# StandBy_converter.net
KiCad netlist of a schematic drawn in Altium Designer
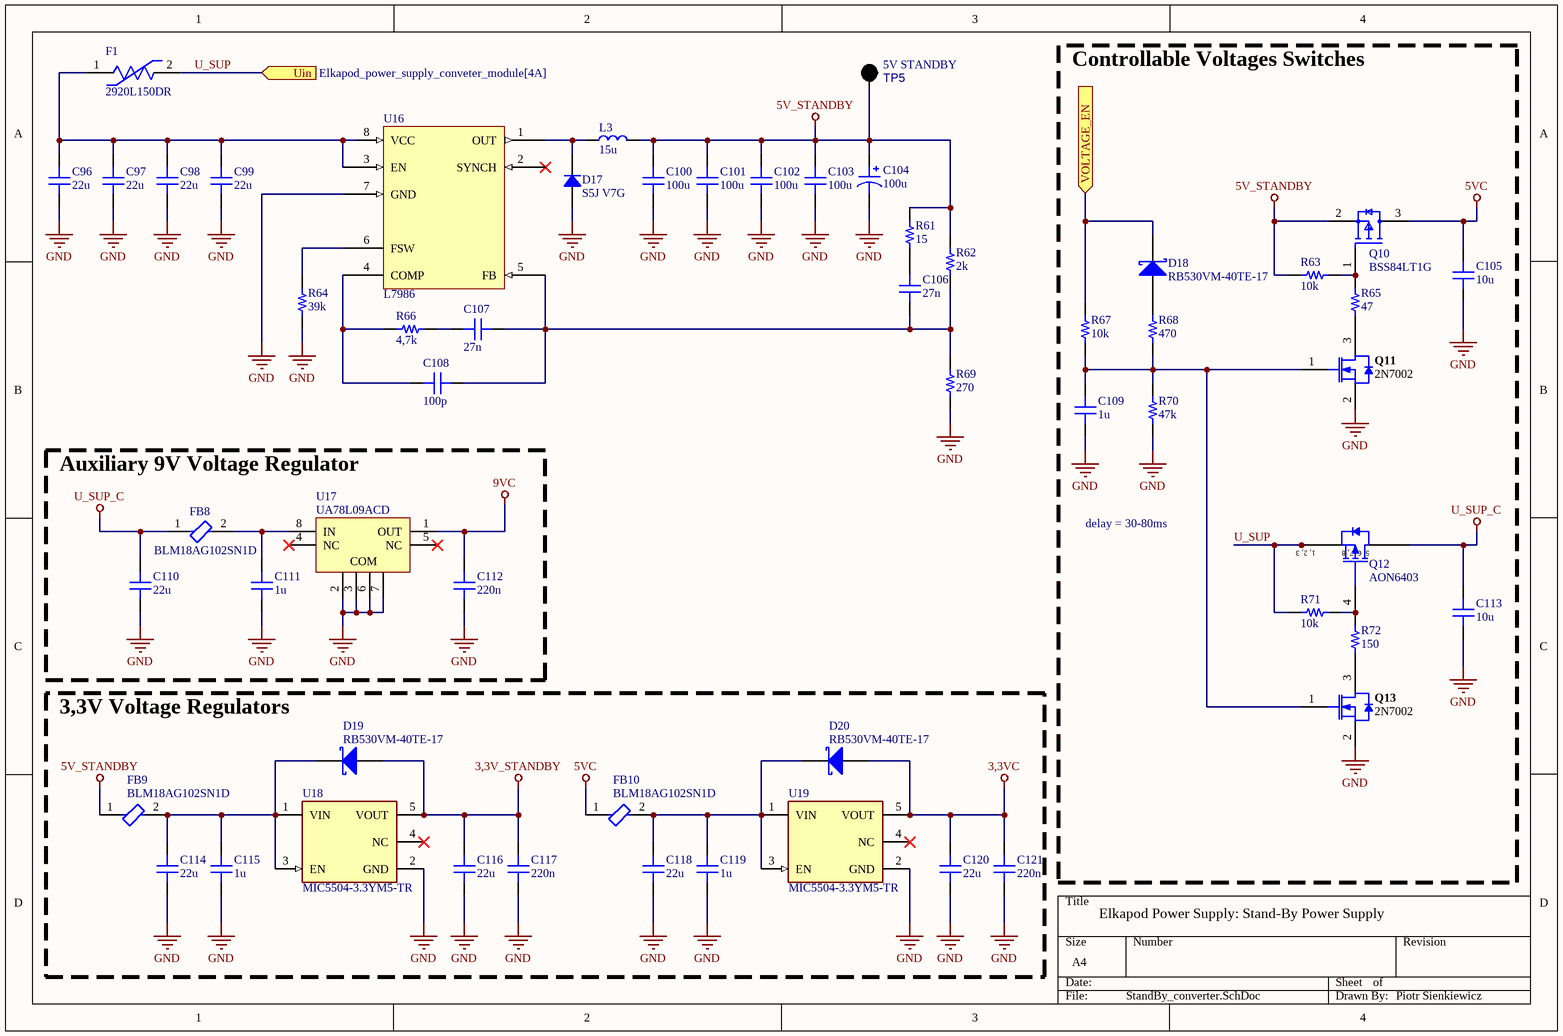
[diagram p0: StandBy_converter.SchDoc]

(export (version "E")
  (design (tool "Eeschema 10.0.6"))
  (components
    (comp (ref "C96")
      (value "22u")
      (footprint "CAP 0805_2012")
      (description "CAP CER 22UF 25V X7R 0805")
      (fields
        (field (name "PART NUMBER") "VJ0805Y684KXQTW1BC")
        (field (name "MANUFACTURER") "Vishay Vitramon")
      )
      (libsource (lib "Celestial Altium Library - altium_library") (part "Capacitor"))
    )
    (comp (ref "C97")
      (value "22u")
      (footprint "CAP 0805_2012")
      (description "CAP CER 22UF 25V X7R 0805")
      (fields
        (field (name "PART NUMBER") "VJ0805Y684KXQTW1BC")
        (field (name "MANUFACTURER") "Vishay Vitramon")
      )
      (libsource (lib "Celestial Altium Library - altium_library") (part "Capacitor"))
    )
    (comp (ref "C98")
      (value "22u")
      (footprint "CAP 0805_2012")
      (description "CAP CER 22UF 25V X7R 0805")
      (fields
        (field (name "PART NUMBER") "VJ0805Y684KXQTW1BC")
        (field (name "MANUFACTURER") "Vishay Vitramon")
      )
      (libsource (lib "Celestial Altium Library - altium_library") (part "Capacitor"))
    )
    (comp (ref "C99")
      (value "22u")
      (footprint "CAP 0805_2012")
      (description "CAP CER 22UF 25V X7R 0805")
      (fields
        (field (name "PART NUMBER") "VJ0805Y684KXQTW1BC")
        (field (name "MANUFACTURER") "Vishay Vitramon")
      )
      (libsource (lib "Celestial Altium Library - altium_library") (part "Capacitor"))
    )
    (comp (ref "C100")
      (value "100u")
      (footprint "CAP 1210_3225 - 1MM")
      (description "CAP CER 1210 100UF 10V X7R")
      (fields (field (name "PART NUMBER") "CAN13X104KARAC7800") (field (name "MANUFACTURER") "KEMET"))
      (libsource (lib "Celestial Altium Library - altium_library") (part "Capacitor"))
    )
    (comp (ref "C101")
      (value "100u")
      (footprint "CAP 1210_3225 - 1MM")
      (description "CAP CER 1210 100UF 10V X7R")
      (fields (field (name "PART NUMBER") "CAN13X104KARAC7800") (field (name "MANUFACTURER") "KEMET"))
      (libsource (lib "Celestial Altium Library - altium_library") (part "Capacitor"))
    )
    (comp (ref "C102")
      (value "100u")
      (footprint "CAP 1210_3225 - 1MM")
      (description "CAP CER 1210 100UF 10V X7R")
      (fields (field (name "PART NUMBER") "CAN13X104KARAC7800") (field (name "MANUFACTURER") "KEMET"))
      (libsource (lib "Celestial Altium Library - altium_library") (part "Capacitor"))
    )
    (comp (ref "C103")
      (value "100u")
      (footprint "CAP 1210_3225 - 1MM")
      (description "CAP CER 1210 100UF 10V X7R")
      (fields (field (name "PART NUMBER") "CAN13X104KARAC7800") (field (name "MANUFACTURER") "KEMET"))
      (libsource (lib "Celestial Altium Library - altium_library") (part "Capacitor"))
    )
    (comp (ref "C104")
      (value "100u")
      (footprint "CAP ALSMD 8.3MM H10.5MM")
      (description "UCD1V101MNL1GS; CAP ALUM 100UF 20% 16V SMD")
      (libsource (lib "Celestial Altium Library - altium_library") (part "Polarised Capacitor"))
    )
    (comp (ref "C105")
      (value "10u")
      (footprint "CAP 0603_1608")
      (description "CAP CER 10uF 35V X5R 0603")
      (fields (field (name "PART NUMBER") "C0603C272F3GAC7867") (field (name "MANUFACTURER") "KEMET"))
      (libsource (lib "Celestial Altium Library - altium_library") (part "Capacitor"))
    )
    (comp (ref "C106")
      (value "27n")
      (footprint "CAP 0603_1608")
      (description "CAP CER 27nF 50V G0C 0603")
      (fields (field (name "PART NUMBER") "C0603C272F3GAC7867") (field (name "MANUFACTURER") "KEMET"))
      (libsource (lib "Celestial Altium Library - altium_library") (part "Capacitor"))
    )
    (comp (ref "C107")
      (value "27n")
      (footprint "CAP 0603_1608")
      (description "CAP CER 27nF 50V G0C 0603")
      (fields (field (name "PART NUMBER") "C0603C272F3GAC7867") (field (name "MANUFACTURER") "KEMET"))
      (libsource (lib "Celestial Altium Library - altium_library") (part "Capacitor"))
    )
    (comp (ref "C108")
      (value "100p")
      (footprint "CAP 0603_1608")
      (description "CAP CER 100pF 50V G0C 0603")
      (fields (field (name "PART NUMBER") "C0603C272F3GAC7867") (field (name "MANUFACTURER") "KEMET"))
      (libsource (lib "Celestial Altium Library - altium_library") (part "Capacitor"))
    )
    (comp (ref "C109")
      (value "1u")
      (footprint "CAP 0603_1608")
      (description "CAP CER 1uF 16V X5R 0603")
      (fields (field (name "PART NUMBER") "C0603C272F3GAC7867") (field (name "MANUFACTURER") "KEMET"))
      (libsource (lib "Celestial Altium Library - altium_library") (part "Capacitor"))
    )
    (comp (ref "C110")
      (value "22u")
      (footprint "CAP 0805_2012")
      (description "CAP CER 22UF 25V X7R 0805")
      (fields
        (field (name "PART NUMBER") "VJ0805Y684KXQTW1BC")
        (field (name "MANUFACTURER") "Vishay Vitramon")
      )
      (libsource (lib "Celestial Altium Library - altium_library") (part "Capacitor"))
    )
    (comp (ref "C111")
      (value "1u")
      (footprint "CAP 0603_1608")
      (description "CAP CER 1uF 25V X5R 0603")
      (fields (field (name "PART NUMBER") "C0603C272F3GAC7867") (field (name "MANUFACTURER") "KEMET"))
      (libsource (lib "Celestial Altium Library - altium_library") (part "Capacitor"))
    )
    (comp (ref "C112")
      (value "220n")
      (footprint "CAP 0603_1608")
      (description "CAP CER 220nF 25V X5R 0603")
      (fields (field (name "PART NUMBER") "C0603C272F3GAC7867") (field (name "MANUFACTURER") "KEMET"))
      (libsource (lib "Celestial Altium Library - altium_library") (part "Capacitor"))
    )
    (comp (ref "C113")
      (value "10u")
      (footprint "CAP 0603_1608")
      (description "CAP CER 10uF 35V X5R 0603")
      (fields (field (name "PART NUMBER") "C0603C272F3GAC7867") (field (name "MANUFACTURER") "KEMET"))
      (libsource (lib "Celestial Altium Library - altium_library") (part "Capacitor"))
    )
    (comp (ref "C114")
      (value "22u")
      (footprint "CAP 0805_2012")
      (description "CAP CER 22UF 25V X7R 0805")
      (fields
        (field (name "PART NUMBER") "VJ0805Y684KXQTW1BC")
        (field (name "MANUFACTURER") "Vishay Vitramon")
      )
      (libsource (lib "Celestial Altium Library - altium_library") (part "Capacitor"))
    )
    (comp (ref "C115")
      (value "1u")
      (footprint "CAP 0603_1608")
      (description "CAP CER 1uF 25V X5R 0603")
      (fields (field (name "PART NUMBER") "C0603C272F3GAC7867") (field (name "MANUFACTURER") "KEMET"))
      (libsource (lib "Celestial Altium Library - altium_library") (part "Capacitor"))
    )
    (comp (ref "C116")
      (value "22u")
      (footprint "CAP 0805_2012")
      (description "CAP CER 22UF 25V X7R 0805")
      (fields
        (field (name "PART NUMBER") "VJ0805Y684KXQTW1BC")
        (field (name "MANUFACTURER") "Vishay Vitramon")
      )
      (libsource (lib "Celestial Altium Library - altium_library") (part "Capacitor"))
    )
    (comp (ref "C117")
      (value "220n")
      (footprint "CAP 0603_1608")
      (description "CAP CER 220nF 25V X5R 0603")
      (fields (field (name "PART NUMBER") "C0603C272F3GAC7867") (field (name "MANUFACTURER") "KEMET"))
      (libsource (lib "Celestial Altium Library - altium_library") (part "Capacitor"))
    )
    (comp (ref "C118")
      (value "22u")
      (footprint "CAP 0805_2012")
      (description "CAP CER 22UF 25V X7R 0805")
      (fields
        (field (name "PART NUMBER") "VJ0805Y684KXQTW1BC")
        (field (name "MANUFACTURER") "Vishay Vitramon")
      )
      (libsource (lib "Celestial Altium Library - altium_library") (part "Capacitor"))
    )
    (comp (ref "C119")
      (value "1u")
      (footprint "CAP 0603_1608")
      (description "CAP CER 1uF 25V X5R 0603")
      (fields (field (name "PART NUMBER") "C0603C272F3GAC7867") (field (name "MANUFACTURER") "KEMET"))
      (libsource (lib "Celestial Altium Library - altium_library") (part "Capacitor"))
    )
    (comp (ref "C120")
      (value "22u")
      (footprint "CAP 0805_2012")
      (description "CAP CER 22UF 25V X7R 0805")
      (fields
        (field (name "PART NUMBER") "VJ0805Y684KXQTW1BC")
        (field (name "MANUFACTURER") "Vishay Vitramon")
      )
      (libsource (lib "Celestial Altium Library - altium_library") (part "Capacitor"))
    )
    (comp (ref "C121")
      (value "220n")
      (footprint "CAP 0603_1608")
      (description "CAP CER 220nF 25V X5R 0603")
      (fields (field (name "PART NUMBER") "C0603C272F3GAC7867") (field (name "MANUFACTURER") "KEMET"))
      (libsource (lib "Celestial Altium Library - altium_library") (part "Capacitor"))
    )
    (comp (ref "D17")
      (value "S5J V7G")
      (footprint "DO214AB SMC")
      (description "DIODE GEN PURP 600V 5A DO214AB")
      (fields (field (name "MANUFACTURER") "Taiwan Semiconductor Corporation"))
      (libsource (lib "Celestial Altium Library - altium_library") (part "Diode"))
    )
    (comp (ref "D18")
      (value "RB530VM-40TE-17")
      (footprint "SOD-323")
      (description "Schottky diode; 0,1A; 40V")
      (fields (field (name "PUBLISHER") "Altium Limited"))
      (libsource (lib "Infineon Discrete Diode") (part "BAS140W"))
    )
    (comp (ref "D19")
      (value "RB530VM-40TE-17")
      (footprint "SOD-323")
      (description "Schottky diode; 0,1A; 40V")
      (fields (field (name "PUBLISHER") "Altium Limited"))
      (libsource (lib "Infineon Discrete Diode") (part "BAS140W"))
    )
    (comp (ref "D20")
      (value "RB530VM-40TE-17")
      (footprint "SOD-323")
      (description "Schottky diode; 0,1A; 40V")
      (fields (field (name "PUBLISHER") "Altium Limited"))
      (libsource (lib "Infineon Discrete Diode") (part "BAS140W"))
    )
    (comp (ref "F1")
      (value "2920L150DR")
      (footprint "FP-2920L150DR-MFG")
      (description "PTC RESET FUSE 33V 1.5A 2920")
      (libsource (lib "Altium Content Vault") (part "fc31388045fc42ab786d6d00b506e9f"))
    )
    (comp (ref "FB8")
      (value "BLM18AG102SN1D")
      (footprint "FP-BLM18-0_15-t0_8-MFG")
      (description "Chip Ferrite Bead, 0603, 1000Ω @ 100MHz, 0.5Ω, 25%, 450mA")
      (fields (field (name "TOLERANCE") "25%"))
      (libsource (lib "Altium Content Vault") (part "5f30dd21d616792df468990f7003faa"))
    )
    (comp (ref "FB9")
      (value "BLM18AG102SN1D")
      (footprint "FP-BLM18-0_15-t0_8-MFG")
      (description "Chip Ferrite Bead, 0603, 1000Ω @ 100MHz, 0.5Ω, 25%, 450mA")
      (fields (field (name "TOLERANCE") "25%"))
      (libsource (lib "Altium Content Vault") (part "5f30dd21d616792df468990f7003faa"))
    )
    (comp (ref "FB10")
      (value "BLM18AG102SN1D")
      (footprint "FP-BLM18-0_15-t0_8-MFG")
      (description "Chip Ferrite Bead, 0603, 1000Ω @ 100MHz, 0.5Ω, 25%, 450mA")
      (fields (field (name "TOLERANCE") "25%"))
      (libsource (lib "Altium Content Vault") (part "5f30dd21d616792df468990f7003faa"))
    )
    (comp (ref "L3")
      (value "15u")
      (footprint "12,5x12,5_INDUCTOR")
      (description "SMD power inductor; Imax = 4,27A; Isat = 5,69A")
      (libsource (lib "My_passive_components") (part "12,5x12,5_INDUCTOR"))
    )
    (comp (ref "Q10")
      (value "BSS84LT1G")
      (footprint "FP-318-08-IPC_A")
      (description "MOSFET P-CH 50V 130MA SOT-23")
      (libsource (lib "Altium Content Vault") (part "1317a8eff0fddff9cd18bdaa032127a"))
    )
    (comp (ref "Q11")
      (value "2N7002")
      (footprint "INF-PG-SOT23_M")
      (fields (field (name "MANUFACTURER") "Infineon"))
      (libsource (lib "Altium Content Vault") (part "INF-NDMOS-GSD-3"))
    )
    (comp (ref "Q12")
      (value "AON6403")
      (footprint "DFN5x6")
      (description "P-MOSFET; 67A; 30V; DFN5x6")
      (libsource (lib "My_transistors") (part "AON6403"))
    )
    (comp (ref "Q13")
      (value "2N7002")
      (footprint "INF-PG-SOT23_M")
      (fields (field (name "MANUFACTURER") "Infineon"))
      (libsource (lib "Altium Content Vault") (part "INF-NDMOS-GSD-3"))
    )
    (comp (ref "R61")
      (value "15")
      (footprint "RES 0603_1608")
      (description "RES 15 OHM 1% 0,1W 0603")
      (fields
        (field (name "PART NUMBER") "RNCS0603BKE10K0")
        (field (name "MANUFACTURER") "Stackpole Electronics Inc")
      )
      (libsource (lib "Celestial Altium Library - altium_library") (part "Resistor"))
    )
    (comp (ref "R62")
      (value "2k")
      (footprint "RES 0603_1608")
      (description "RES 2K OHM 1% 0,1W 0603")
      (fields
        (field (name "PART NUMBER") "RNCS0603BKE10K0")
        (field (name "MANUFACTURER") "Stackpole Electronics Inc")
      )
      (libsource (lib "Celestial Altium Library - altium_library") (part "Resistor"))
    )
    (comp (ref "R63")
      (value "10k")
      (footprint "RES 0603_1608")
      (description "RES 10K OHM 1% 0,1W 0603")
      (fields
        (field (name "PART NUMBER") "RNCS0603BKE10K0")
        (field (name "MANUFACTURER") "Stackpole Electronics Inc")
      )
      (libsource (lib "Celestial Altium Library - altium_library") (part "Resistor"))
    )
    (comp (ref "R64")
      (value "39k")
      (footprint "RES 0603_1608")
      (description "RES 39K OHM 1% 0,1W 0603")
      (fields
        (field (name "PART NUMBER") "RNCS0603BKE10K0")
        (field (name "MANUFACTURER") "Stackpole Electronics Inc")
      )
      (libsource (lib "Celestial Altium Library - altium_library") (part "Resistor"))
    )
    (comp (ref "R65")
      (value "47")
      (footprint "RES 0603_1608")
      (description "RES 47 OHM 1% 0,1W 0603")
      (fields
        (field (name "PART NUMBER") "RNCS0603BKE10K0")
        (field (name "MANUFACTURER") "Stackpole Electronics Inc")
      )
      (libsource (lib "Celestial Altium Library - altium_library") (part "Resistor"))
    )
    (comp (ref "R66")
      (value "4,7k")
      (footprint "RES 0603_1608")
      (description "RES 4,7K OHM 1% 0,1W 0603")
      (fields
        (field (name "PART NUMBER") "RNCS0603BKE10K0")
        (field (name "MANUFACTURER") "Stackpole Electronics Inc")
      )
      (libsource (lib "Celestial Altium Library - altium_library") (part "Resistor"))
    )
    (comp (ref "R67")
      (value "10k")
      (footprint "RES 0603_1608")
      (description "RES 10K OHM 1% 0,1W 0603")
      (fields
        (field (name "PART NUMBER") "RNCS0603BKE10K0")
        (field (name "MANUFACTURER") "Stackpole Electronics Inc")
      )
      (libsource (lib "Celestial Altium Library - altium_library") (part "Resistor"))
    )
    (comp (ref "R68")
      (value "470")
      (footprint "RES 0603_1608")
      (description "RES 470 OHM 1% 0,1W 0603")
      (fields
        (field (name "PART NUMBER") "RNCS0603BKE10K0")
        (field (name "MANUFACTURER") "Stackpole Electronics Inc")
      )
      (libsource (lib "Celestial Altium Library - altium_library") (part "Resistor"))
    )
    (comp (ref "R69")
      (value "270")
      (footprint "RES 0603_1608")
      (description "RES 270 OHM 1% 0,1W 0603")
      (fields
        (field (name "PART NUMBER") "RNCS0603BKE10K0")
        (field (name "MANUFACTURER") "Stackpole Electronics Inc")
      )
      (libsource (lib "Celestial Altium Library - altium_library") (part "Resistor"))
    )
    (comp (ref "R70")
      (value "47k")
      (footprint "RES 0603_1608")
      (description "RES 47K OHM 1% 0,1W 0603")
      (fields
        (field (name "PART NUMBER") "RNCS0603BKE10K0")
        (field (name "MANUFACTURER") "Stackpole Electronics Inc")
      )
      (libsource (lib "Celestial Altium Library - altium_library") (part "Resistor"))
    )
    (comp (ref "R71")
      (value "10k")
      (footprint "RES 0603_1608")
      (description "RES 10K OHM 1% 0,1W 0603")
      (fields
        (field (name "PART NUMBER") "RNCS0603BKE10K0")
        (field (name "MANUFACTURER") "Stackpole Electronics Inc")
      )
      (libsource (lib "Celestial Altium Library - altium_library") (part "Resistor"))
    )
    (comp (ref "R72")
      (value "150")
      (footprint "RES 0603_1608")
      (description "RES 150 OHM 1% 0,1W 0603")
      (fields
        (field (name "PART NUMBER") "RNCS0603BKE10K0")
        (field (name "MANUFACTURER") "Stackpole Electronics Inc")
      )
      (libsource (lib "Celestial Altium Library - altium_library") (part "Resistor"))
    )
    (comp (ref "TP5")
      (value "5V STANDBY")
      (footprint "Keystone_5006_BLACK")
      (description "Keystone 5006 Test Point (BLACK)")
      (libsource (lib "test_points") (part "Keystone 5006 Test Point"))
    )
    (comp (ref "U16")
      (value "L7986")
      (footprint "HSOP8_L")
      (description "3 A step-down switching regulator; HSOP8")
      (libsource (lib "My_integrated_circuits") (part "L7986"))
    )
    (comp (ref "U17")
      (value "UA78L09ACD")
      (footprint "D0008A_N")
      (fields (field (name "MANUFACTURER") "Texas Instruments"))
      (libsource (lib "Altium Content Vault") (part "TI-UA78L09AD8"))
    )
    (comp (ref "U18")
      (value "MIC5504-3.3YM5-TR")
      (footprint "FP-SOT23-5LD-PL-1-MFG")
      (description "IC REG LINEAR 3.3V 300MA SOT23-5")
      (libsource (lib "Altium Content Vault") (part "96048095611b4a9579e1e315950d302"))
    )
    (comp (ref "U19")
      (value "MIC5504-3.3YM5-TR")
      (footprint "FP-SOT23-5LD-PL-1-MFG")
      (description "IC REG LINEAR 3.3V 300MA SOT23-5")
      (libsource (lib "Altium Content Vault") (part "96048095611b4a9579e1e315950d302"))
    )
  )
  (nets
    (net (code "1") (name "/U_SUP") (class "Default")
      (node (ref "F1") (pin "2") (pinfunction "2_2") (pintype "passive"))
      (node (ref "Q12") (pin "1") (pinfunction "S_1") (pintype "passive"))
      (node (ref "Q12") (pin "2") (pinfunction "S_2") (pintype "passive"))
      (node (ref "Q12") (pin "3") (pinfunction "S_3") (pintype "passive"))
      (node (ref "R71") (pin "1") (pinfunction "1_1") (pintype "passive"))
    )
    (net (code "2") (name "/VOLTAGE_EN") (class "Default")
      (node (ref "D18") (pin "1") (pinfunction "K_1") (pintype "passive"))
      (node (ref "R67") (pin "2") (pinfunction "2_2") (pintype "passive"))
    )
    (net (code "3") (name "3,3VC") (class "Default")
      (node (ref "C120") (pin "2") (pinfunction "2_2") (pintype "passive"))
      (node (ref "C121") (pin "2") (pinfunction "2_2") (pintype "passive"))
      (node (ref "D20") (pin "2") (pinfunction "A_2") (pintype "passive"))
      (node (ref "U19") (pin "5") (pinfunction "VOUT_5") (pintype "power_in"))
    )
    (net (code "4") (name "3,3V_STANDBY") (class "Default")
      (node (ref "C116") (pin "2") (pinfunction "2_2") (pintype "passive"))
      (node (ref "C117") (pin "2") (pinfunction "2_2") (pintype "passive"))
      (node (ref "D19") (pin "2") (pinfunction "A_2") (pintype "passive"))
      (node (ref "U18") (pin "5") (pinfunction "VOUT_5") (pintype "power_in"))
    )
    (net (code "5") (name "5VC") (class "Default")
      (node (ref "C105") (pin "2") (pinfunction "2_2") (pintype "passive"))
      (node (ref "FB10") (pin "1") (pinfunction "1_1") (pintype "passive"))
      (node (ref "Q10") (pin "3") (pinfunction "D_3") (pintype "passive"))
    )
    (net (code "6") (name "5V_STANDBY") (class "Default")
      (node (ref "C100") (pin "2") (pinfunction "2_2") (pintype "passive"))
      (node (ref "C101") (pin "2") (pinfunction "2_2") (pintype "passive"))
      (node (ref "C102") (pin "2") (pinfunction "2_2") (pintype "passive"))
      (node (ref "C103") (pin "2") (pinfunction "2_2") (pintype "passive"))
      (node (ref "C104") (pin "1") (pinfunction "1_1") (pintype "passive"))
      (node (ref "FB9") (pin "1") (pinfunction "1_1") (pintype "passive"))
      (node (ref "L3") (pin "2") (pinfunction "2_2") (pintype "passive"))
      (node (ref "Q10") (pin "2") (pinfunction "S_2") (pintype "passive"))
      (node (ref "R61") (pin "2") (pinfunction "2_2") (pintype "passive"))
      (node (ref "R62") (pin "2") (pinfunction "2_2") (pintype "passive"))
      (node (ref "R63") (pin "1") (pinfunction "1_1") (pintype "passive"))
      (node (ref "TP5") (pin "0") (pinfunction "0_0") (pintype "passive"))
    )
    (net (code "7") (name "9VC") (class "Default")
      (node (ref "C112") (pin "2") (pinfunction "2_2") (pintype "passive"))
      (node (ref "U17") (pin "1") (pinfunction "OUT_1") (pintype "power_in"))
    )
    (net (code "8") (name "GND") (class "Default")
      (node (ref "C100") (pin "1") (pinfunction "1_1") (pintype "passive"))
      (node (ref "C101") (pin "1") (pinfunction "1_1") (pintype "passive"))
      (node (ref "C102") (pin "1") (pinfunction "1_1") (pintype "passive"))
      (node (ref "C103") (pin "1") (pinfunction "1_1") (pintype "passive"))
      (node (ref "C104") (pin "2") (pinfunction "2_2") (pintype "passive"))
      (node (ref "C105") (pin "1") (pinfunction "1_1") (pintype "passive"))
      (node (ref "C109") (pin "1") (pinfunction "1_1") (pintype "passive"))
      (node (ref "C110") (pin "1") (pinfunction "1_1") (pintype "passive"))
      (node (ref "C111") (pin "1") (pinfunction "1_1") (pintype "passive"))
      (node (ref "C112") (pin "1") (pinfunction "1_1") (pintype "passive"))
      (node (ref "C113") (pin "1") (pinfunction "1_1") (pintype "passive"))
      (node (ref "C114") (pin "1") (pinfunction "1_1") (pintype "passive"))
      (node (ref "C115") (pin "1") (pinfunction "1_1") (pintype "passive"))
      (node (ref "C116") (pin "1") (pinfunction "1_1") (pintype "passive"))
      (node (ref "C117") (pin "1") (pinfunction "1_1") (pintype "passive"))
      (node (ref "C118") (pin "1") (pinfunction "1_1") (pintype "passive"))
      (node (ref "C119") (pin "1") (pinfunction "1_1") (pintype "passive"))
      (node (ref "C120") (pin "1") (pinfunction "1_1") (pintype "passive"))
      (node (ref "C121") (pin "1") (pinfunction "1_1") (pintype "passive"))
      (node (ref "C96") (pin "1") (pinfunction "1_1") (pintype "passive"))
      (node (ref "C97") (pin "1") (pinfunction "1_1") (pintype "passive"))
      (node (ref "C98") (pin "1") (pinfunction "1_1") (pintype "passive"))
      (node (ref "C99") (pin "1") (pinfunction "1_1") (pintype "passive"))
      (node (ref "D17") (pin "1") (pinfunction "1_1") (pintype "passive"))
      (node (ref "Q11") (pin "2") (pinfunction "SOURCE_2") (pintype "passive"))
      (node (ref "Q13") (pin "2") (pinfunction "SOURCE_2") (pintype "passive"))
      (node (ref "R64") (pin "1") (pinfunction "1_1") (pintype "passive"))
      (node (ref "R69") (pin "1") (pinfunction "1_1") (pintype "passive"))
      (node (ref "R70") (pin "1") (pinfunction "1_1") (pintype "passive"))
      (node (ref "U16") (pin "7") (pinfunction "GND_7") (pintype "input"))
      (node (ref "U17") (pin "2") (pinfunction "GND_2") (pintype "power_in"))
      (node (ref "U17") (pin "3") (pinfunction "GND_3") (pintype "power_in"))
      (node (ref "U17") (pin "6") (pinfunction "GND_6") (pintype "power_in"))
      (node (ref "U17") (pin "7") (pinfunction "GND_7") (pintype "power_in"))
      (node (ref "U18") (pin "2") (pinfunction "GND_2") (pintype "power_in"))
      (node (ref "U19") (pin "2") (pinfunction "GND_2") (pintype "power_in"))
    )
    (net (code "9") (name "Net-(C106-Pad2)") (class "Default")
      (node (ref "C106") (pin "2") (pinfunction "2_2") (pintype "passive"))
      (node (ref "R61") (pin "1") (pinfunction "1_1") (pintype "passive"))
    )
    (net (code "10") (name "Net-(C107-Pad2)") (class "Default")
      (node (ref "C107") (pin "2") (pinfunction "2_2") (pintype "passive"))
      (node (ref "R66") (pin "1") (pinfunction "1_1") (pintype "passive"))
    )
    (net (code "11") (name "Net-(D18-A)") (class "Default")
      (node (ref "D18") (pin "2") (pinfunction "A_2") (pintype "passive"))
      (node (ref "R68") (pin "2") (pinfunction "2_2") (pintype "passive"))
    )
    (net (code "12") (name "Net-(D19-K)") (class "Default")
      (node (ref "C114") (pin "2") (pinfunction "2_2") (pintype "passive"))
      (node (ref "C115") (pin "2") (pinfunction "2_2") (pintype "passive"))
      (node (ref "D19") (pin "1") (pinfunction "K_1") (pintype "passive"))
      (node (ref "FB9") (pin "2") (pinfunction "2_2") (pintype "passive"))
      (node (ref "U18") (pin "1") (pinfunction "VIN_1") (pintype "power_in"))
      (node (ref "U18") (pin "3") (pinfunction "EN_3") (pintype "input"))
    )
    (net (code "13") (name "Net-(D20-K)") (class "Default")
      (node (ref "C118") (pin "2") (pinfunction "2_2") (pintype "passive"))
      (node (ref "C119") (pin "2") (pinfunction "2_2") (pintype "passive"))
      (node (ref "D20") (pin "1") (pinfunction "K_1") (pintype "passive"))
      (node (ref "FB10") (pin "2") (pinfunction "2_2") (pintype "passive"))
      (node (ref "U19") (pin "1") (pinfunction "VIN_1") (pintype "power_in"))
      (node (ref "U19") (pin "3") (pinfunction "EN_3") (pintype "input"))
    )
    (net (code "14") (name "Net-(Q10-G)") (class "Default")
      (node (ref "Q10") (pin "1") (pinfunction "G_1") (pintype "passive"))
      (node (ref "R63") (pin "2") (pinfunction "2_2") (pintype "passive"))
      (node (ref "R65") (pin "1") (pinfunction "1_1") (pintype "passive"))
    )
    (net (code "15") (name "Net-(Q11-DRAIN)") (class "Default")
      (node (ref "Q11") (pin "3") (pinfunction "DRAIN_3") (pintype "passive"))
      (node (ref "R65") (pin "2") (pinfunction "2_2") (pintype "passive"))
    )
    (net (code "16") (name "Net-(Q11-GATE)") (class "Default")
      (node (ref "C109") (pin "2") (pinfunction "2_2") (pintype "passive"))
      (node (ref "Q11") (pin "1") (pinfunction "GATE_1") (pintype "passive"))
      (node (ref "Q13") (pin "1") (pinfunction "GATE_1") (pintype "passive"))
      (node (ref "R67") (pin "1") (pinfunction "1_1") (pintype "passive"))
      (node (ref "R68") (pin "1") (pinfunction "1_1") (pintype "passive"))
      (node (ref "R70") (pin "2") (pinfunction "2_2") (pintype "passive"))
    )
    (net (code "17") (name "Net-(Q12-G)") (class "Default")
      (node (ref "Q12") (pin "4") (pinfunction "G_4") (pintype "passive"))
      (node (ref "R71") (pin "2") (pinfunction "2_2") (pintype "passive"))
      (node (ref "R72") (pin "1") (pinfunction "1_1") (pintype "passive"))
    )
    (net (code "18") (name "Net-(Q13-DRAIN)") (class "Default")
      (node (ref "Q13") (pin "3") (pinfunction "DRAIN_3") (pintype "passive"))
      (node (ref "R72") (pin "2") (pinfunction "2_2") (pintype "passive"))
    )
    (net (code "19") (name "Net-(U16-COMP)") (class "Default")
      (node (ref "C108") (pin "2") (pinfunction "2_2") (pintype "passive"))
      (node (ref "R66") (pin "2") (pinfunction "2_2") (pintype "passive"))
      (node (ref "U16") (pin "4") (pinfunction "COMP_4") (pintype "passive"))
    )
    (net (code "20") (name "Net-(U16-EN)") (class "Default")
      (node (ref "C96") (pin "2") (pinfunction "2_2") (pintype "passive"))
      (node (ref "C97") (pin "2") (pinfunction "2_2") (pintype "passive"))
      (node (ref "C98") (pin "2") (pinfunction "2_2") (pintype "passive"))
      (node (ref "C99") (pin "2") (pinfunction "2_2") (pintype "passive"))
      (node (ref "F1") (pin "1") (pinfunction "1_1") (pintype "passive"))
      (node (ref "U16") (pin "3") (pinfunction "EN_3") (pintype "input"))
      (node (ref "U16") (pin "8") (pinfunction "VCC_8") (pintype "input"))
    )
    (net (code "21") (name "Net-(U16-FB)") (class "Default")
      (node (ref "C106") (pin "1") (pinfunction "1_1") (pintype "passive"))
      (node (ref "C107") (pin "1") (pinfunction "1_1") (pintype "passive"))
      (node (ref "C108") (pin "1") (pinfunction "1_1") (pintype "passive"))
      (node (ref "R62") (pin "1") (pinfunction "1_1") (pintype "passive"))
      (node (ref "R69") (pin "2") (pinfunction "2_2") (pintype "passive"))
      (node (ref "U16") (pin "5") (pinfunction "FB_5") (pintype "input"))
    )
    (net (code "22") (name "Net-(U16-FSW)") (class "Default")
      (node (ref "R64") (pin "2") (pinfunction "2_2") (pintype "passive"))
      (node (ref "U16") (pin "6") (pinfunction "FSW_6") (pintype "passive"))
    )
    (net (code "23") (name "Net-(U16-OUT)") (class "Default")
      (node (ref "D17") (pin "2") (pinfunction "2_2") (pintype "passive"))
      (node (ref "L3") (pin "1") (pinfunction "1_1") (pintype "passive"))
      (node (ref "U16") (pin "1") (pinfunction "OUT_1") (pintype "output"))
    )
    (net (code "24") (name "Net-(U17-IN)") (class "Default")
      (node (ref "C111") (pin "2") (pinfunction "2_2") (pintype "passive"))
      (node (ref "FB8") (pin "2") (pinfunction "2_2") (pintype "passive"))
      (node (ref "U17") (pin "8") (pinfunction "IN_8") (pintype "power_in"))
    )
    (net (code "25") (name "U_SUP_C") (class "Default")
      (node (ref "C110") (pin "2") (pinfunction "2_2") (pintype "passive"))
      (node (ref "C113") (pin "2") (pinfunction "2_2") (pintype "passive"))
      (node (ref "FB8") (pin "1") (pinfunction "1_1") (pintype "passive"))
      (node (ref "Q12") (pin "5") (pinfunction "D_5") (pintype "passive"))
    )
    (net (code "26") (name "unconnected-(U16-SYNCH-Pad2)") (class "Default")
      (node (ref "U16") (pin "2") (pinfunction "SYNCH_2") (pintype "input+no_connect"))
    )
    (net (code "27") (name "unconnected-(U17-NC-Pad4)") (class "Default")
      (node (ref "U17") (pin "4") (pinfunction "NC_4") (pintype "passive+no_connect"))
    )
    (net (code "28") (name "unconnected-(U17-NC-Pad5)") (class "Default")
      (node (ref "U17") (pin "5") (pinfunction "NC_5") (pintype "passive+no_connect"))
    )
    (net (code "29") (name "unconnected-(U18-NC-Pad4)") (class "Default")
      (node (ref "U18") (pin "4") (pinfunction "NC_4") (pintype "passive+no_connect"))
    )
    (net (code "30") (name "unconnected-(U19-NC-Pad4)") (class "Default")
      (node (ref "U19") (pin "4") (pinfunction "NC_4") (pintype "passive+no_connect"))
    )
  )
)
